# ESP.net
KiCad netlist of a schematic drawn in Altium Designer
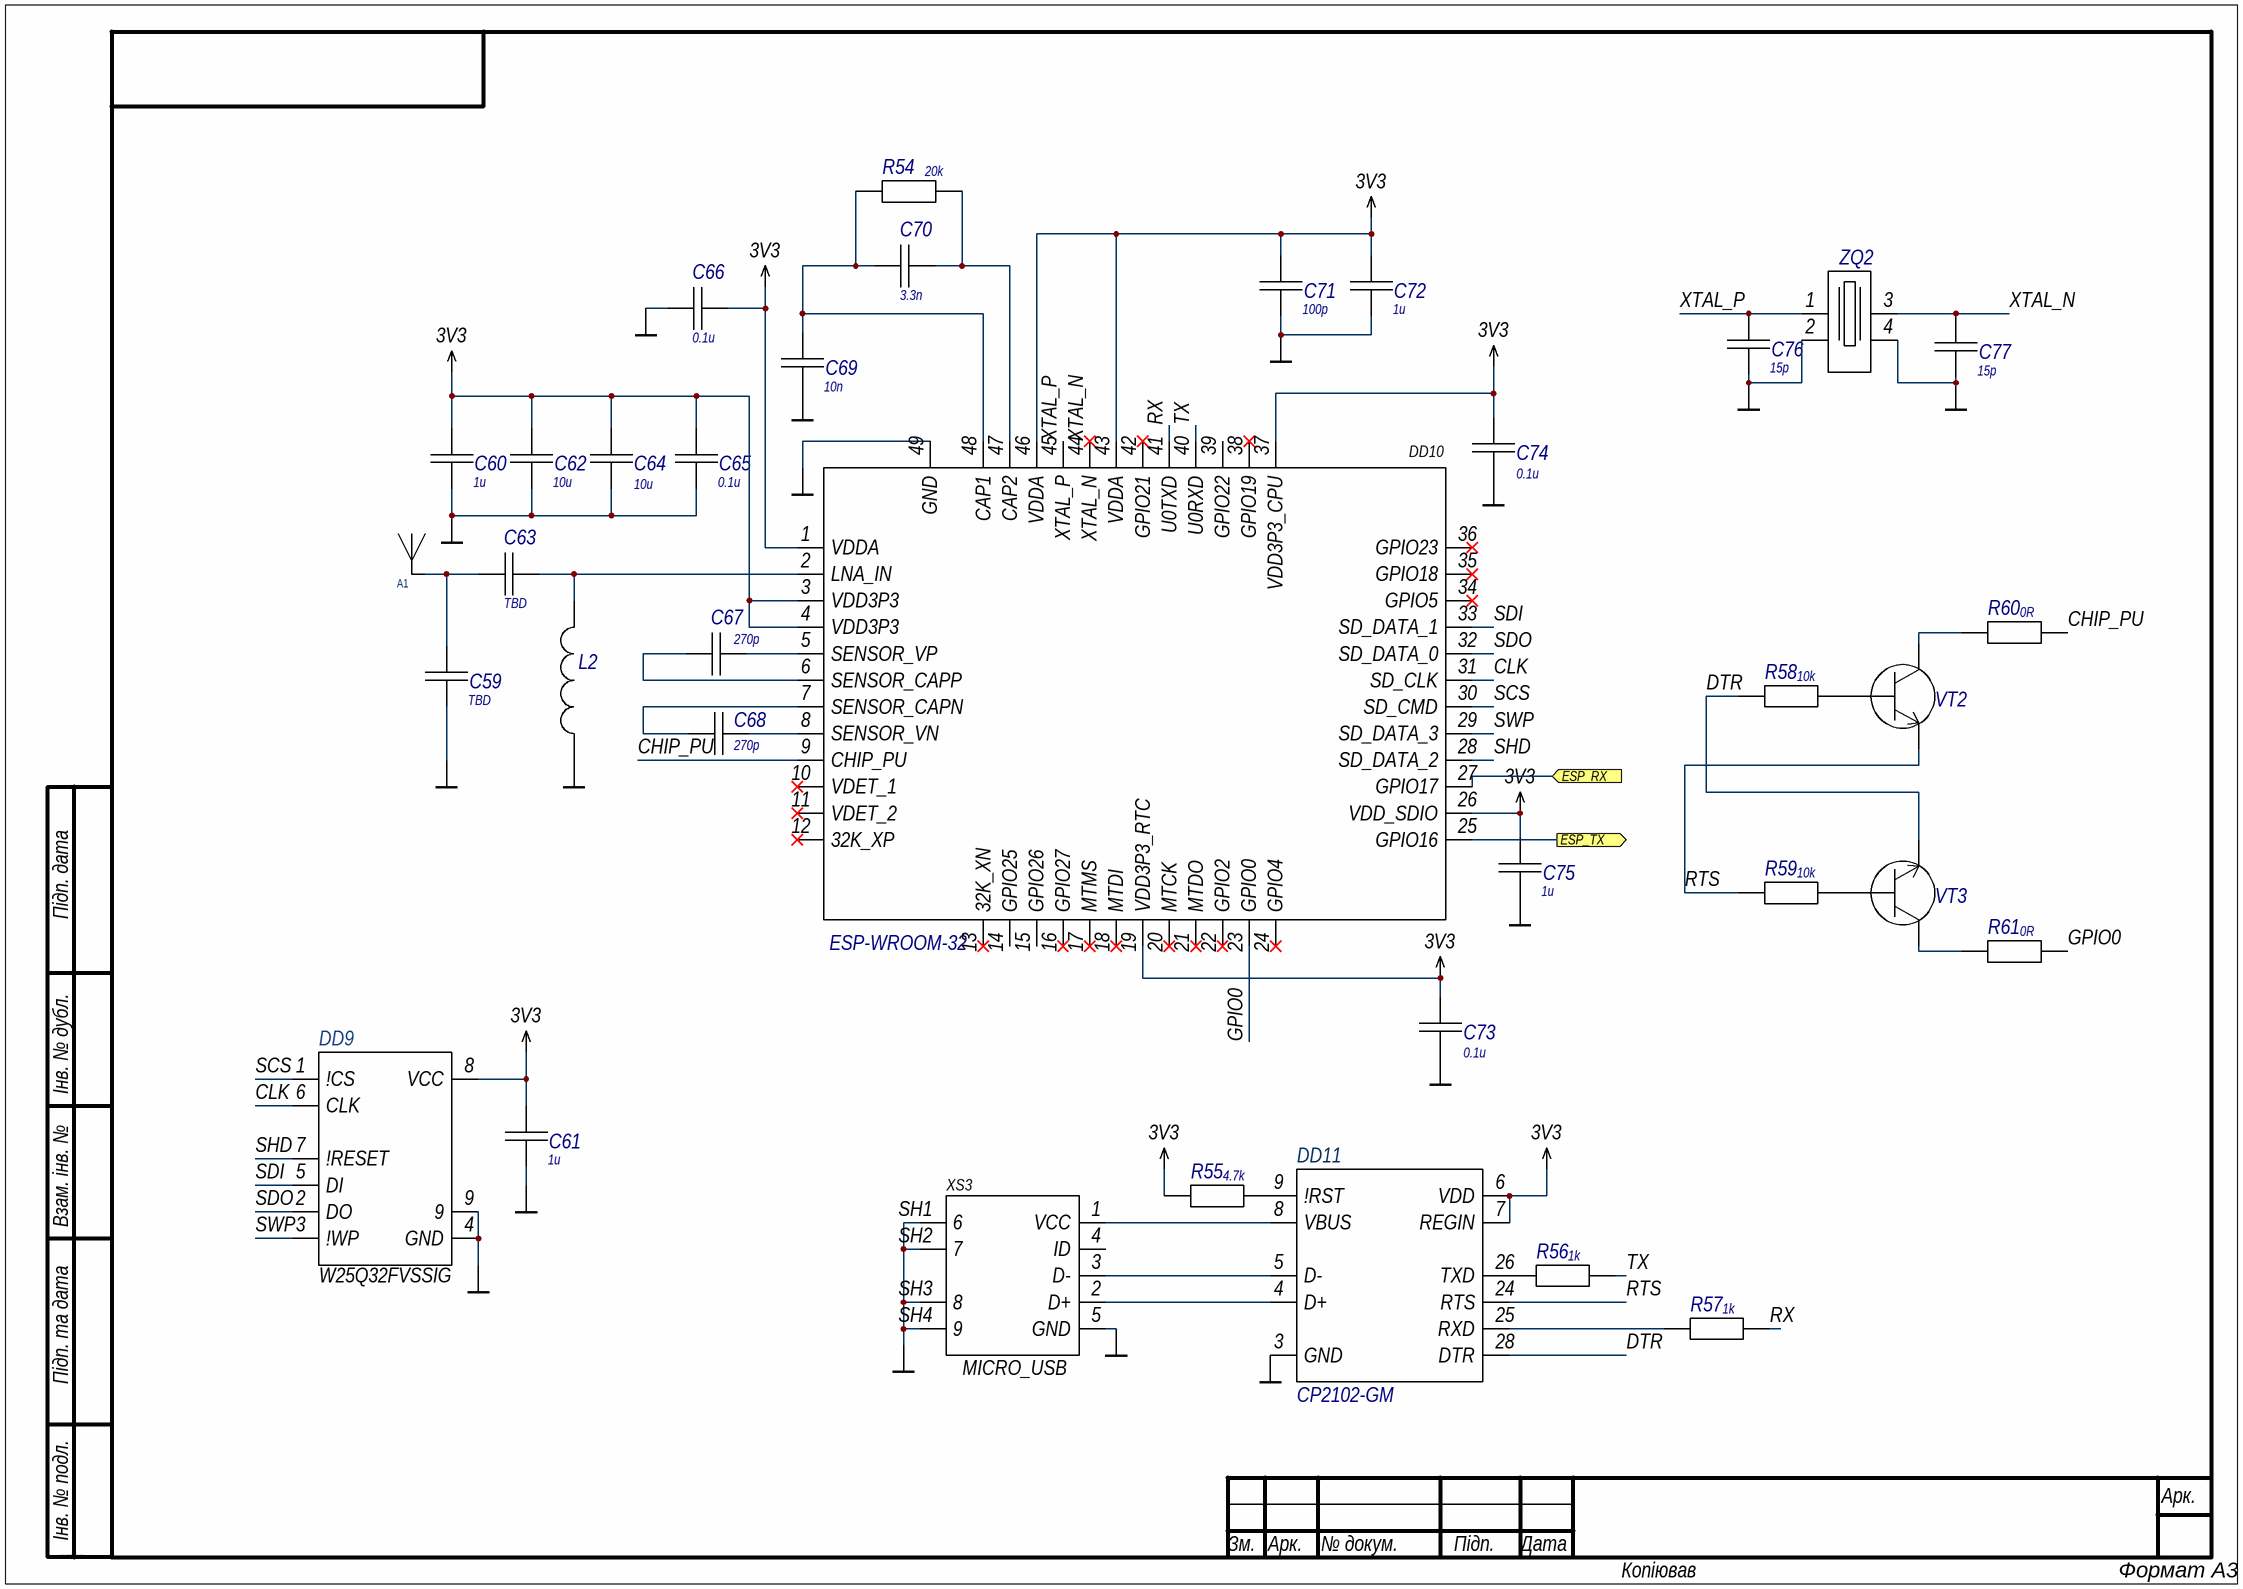
[diagram p0: ESP.SchDoc]

(export (version "E")
  (design (tool "Eeschema 10.0.6"))
  (components
    (comp (ref "A1")
      (value "Antenna-1-Pin")
      (description "SMA, Through-Hole")
      (libsource (lib "Schlib1") (part "Antenna-1-Pin"))
    )
    (comp (ref "C59")
      (value "TBD")
      (footprint "C_0603")
      (fields
        (field (name "VOLTAGE") "50 В")
        (field (name "TOLERANCE") "10%")
        (field (name "MANUFACTURER") "TDK Corporation")
      )
      (libsource (lib "Schlib1") (part "C_0603"))
    )
    (comp (ref "C60")
      (value "1u")
      (footprint "C_0603")
      (fields
        (field (name "VOLTAGE") "50 В")
        (field (name "TOLERANCE") "10%")
        (field (name "MANUFACTURER") "TDK Corporation")
      )
      (libsource (lib "Schlib1") (part "C_0603"))
    )
    (comp (ref "C61")
      (value "1u")
      (footprint "C_0603")
      (fields
        (field (name "VOLTAGE") "50 В")
        (field (name "TOLERANCE") "10%")
        (field (name "MANUFACTURER") "TDK Corporation")
      )
      (libsource (lib "Schlib1") (part "C_0603"))
    )
    (comp (ref "C62")
      (value "10u")
      (footprint "C_0603")
      (fields
        (field (name "VOLTAGE") "50 В")
        (field (name "TOLERANCE") "10%")
        (field (name "MANUFACTURER") "TDK Corporation")
      )
      (libsource (lib "Schlib1") (part "C_0603"))
    )
    (comp (ref "C63")
      (value "TBD")
      (footprint "C_0603")
      (fields
        (field (name "VOLTAGE") "50 В")
        (field (name "TOLERANCE") "10%")
        (field (name "MANUFACTURER") "TDK Corporation")
      )
      (libsource (lib "Schlib1") (part "C_0603"))
    )
    (comp (ref "C64")
      (value "10u")
      (footprint "C_0603")
      (fields
        (field (name "VOLTAGE") "50 В")
        (field (name "TOLERANCE") "10%")
        (field (name "MANUFACTURER") "TDK Corporation")
      )
      (libsource (lib "Schlib1") (part "C_0603"))
    )
    (comp (ref "C65")
      (value "0.1u")
      (footprint "C_0603")
      (fields
        (field (name "VOLTAGE") "50 В")
        (field (name "TOLERANCE") "10%")
        (field (name "MANUFACTURER") "TDK Corporation")
      )
      (libsource (lib "Schlib1") (part "C_0603"))
    )
    (comp (ref "C66")
      (value "0.1u")
      (footprint "C_0603")
      (fields
        (field (name "VOLTAGE") "50 В")
        (field (name "TOLERANCE") "10%")
        (field (name "MANUFACTURER") "TDK Corporation")
      )
      (libsource (lib "Schlib1") (part "C_0603"))
    )
    (comp (ref "C67")
      (value "270p")
      (footprint "C_0603")
      (fields
        (field (name "VOLTAGE") "50 В")
        (field (name "TOLERANCE") "10%")
        (field (name "MANUFACTURER") "TDK Corporation")
      )
      (libsource (lib "Schlib1") (part "C_0603"))
    )
    (comp (ref "C68")
      (value "270p")
      (footprint "C_0603")
      (fields
        (field (name "VOLTAGE") "50 В")
        (field (name "TOLERANCE") "10%")
        (field (name "MANUFACTURER") "TDK Corporation")
      )
      (libsource (lib "Schlib1") (part "C_0603"))
    )
    (comp (ref "C69")
      (value "10n")
      (footprint "C_0603")
      (fields
        (field (name "VOLTAGE") "50 В")
        (field (name "TOLERANCE") "10%")
        (field (name "MANUFACTURER") "TDK Corporation")
      )
      (libsource (lib "Schlib1") (part "C_0603"))
    )
    (comp (ref "C70")
      (value "3.3n")
      (footprint "C_0603")
      (fields
        (field (name "VOLTAGE") "50 В")
        (field (name "TOLERANCE") "10%")
        (field (name "MANUFACTURER") "TDK Corporation")
      )
      (libsource (lib "Schlib1") (part "C_0603"))
    )
    (comp (ref "C71")
      (value "100p")
      (footprint "C_0603")
      (fields
        (field (name "VOLTAGE") "50 В")
        (field (name "TOLERANCE") "10%")
        (field (name "MANUFACTURER") "TDK Corporation")
      )
      (libsource (lib "Schlib1") (part "C_0603"))
    )
    (comp (ref "C72")
      (value "1u")
      (footprint "C_0603")
      (fields
        (field (name "VOLTAGE") "50 В")
        (field (name "TOLERANCE") "10%")
        (field (name "MANUFACTURER") "TDK Corporation")
      )
      (libsource (lib "Schlib1") (part "C_0603"))
    )
    (comp (ref "C73")
      (value "0.1u")
      (footprint "C_0603")
      (fields
        (field (name "VOLTAGE") "50 В")
        (field (name "TOLERANCE") "10%")
        (field (name "MANUFACTURER") "TDK Corporation")
      )
      (libsource (lib "Schlib1") (part "C_0603"))
    )
    (comp (ref "C74")
      (value "0.1u")
      (footprint "C_0603")
      (fields
        (field (name "VOLTAGE") "50 В")
        (field (name "TOLERANCE") "10%")
        (field (name "MANUFACTURER") "TDK Corporation")
      )
      (libsource (lib "Schlib1") (part "C_0603"))
    )
    (comp (ref "C75")
      (value "1u")
      (footprint "C_0603")
      (fields
        (field (name "VOLTAGE") "50 В")
        (field (name "TOLERANCE") "10%")
        (field (name "MANUFACTURER") "TDK Corporation")
      )
      (libsource (lib "Schlib1") (part "C_0603"))
    )
    (comp (ref "C76")
      (value "15p")
      (footprint "C_0603")
      (fields
        (field (name "VOLTAGE") "50 В")
        (field (name "TOLERANCE") "10%")
        (field (name "MANUFACTURER") "TDK Corporation")
      )
      (libsource (lib "Schlib1") (part "C_0603"))
    )
    (comp (ref "C77")
      (value "15p")
      (footprint "C_0603")
      (fields
        (field (name "VOLTAGE") "50 В")
        (field (name "TOLERANCE") "10%")
        (field (name "MANUFACTURER") "TDK Corporation")
      )
      (libsource (lib "Schlib1") (part "C_0603"))
    )
    (comp (ref "DD9")
      (value "W25Q32FVSSIG")
      (footprint "W25QxxxJVEIQ-127P800X80_MED")
      (description "FLASH - NOR Memory IC 256Mb SPI - Quad I/O, QPI 133 MHz 8-WSON")
      (fields (field (name "MANUFACTURER") "Winbond Electronics") (field (name "PART NUMBER") "W25Q32FVSSIG"))
      (libsource (lib "Schlib1") (part "W25Q256JVEI1"))
    )
    (comp (ref "DD10")
      (value "ESP-WROOM-32 Espressif Systems")
      (fields (field (name "NAME") "ESP-WROOM-32") (field (name "MANUFACTURER") "Espressif Systems"))
      (libsource (lib "Schlib1") (part "ESP32-DOWDQ6"))
    )
    (comp (ref "DD11")
      (value "CP2102-GM")
      (footprint "QFN-28_5x5mm")
      (description "USB 2.0 to UART, 28-QFN (5x5)")
      (fields (field (name "MANUFACTURER") "Silicon Labs") (field (name "PART NUMBER") "CP2102-GM"))
      (libsource (lib "Schlib1") (part "CP2102-GM"))
    )
    (comp (ref "L2")
      (value "FCM 1608KF-601T03")
      (footprint "FB0603")
      (fields (field (name "MANUFACTURER") "TAI-TECH Advanced Electronics Co., Ltd."))
      (libsource (lib "Schlib1") (part "induction"))
    )
    (comp (ref "R54")
      (value "20k")
      (footprint "R0_0603")
      (fields
        (field (name "POWER") "0 В")
        (field (name "TOLERANCE") "1%")
        (field (name "MANUFACTURER") "Keystone Electronics")
      )
      (libsource (lib "Schlib1") (part "R_0603"))
    )
    (comp (ref "R55")
      (value "4.7k")
      (footprint "R0_0603")
      (fields
        (field (name "POWER") "0 В")
        (field (name "TOLERANCE") "1%")
        (field (name "MANUFACTURER") "Keystone Electronics")
      )
      (libsource (lib "Schlib1") (part "R_0603"))
    )
    (comp (ref "R56")
      (value "1k")
      (footprint "R0_0603")
      (fields
        (field (name "POWER") "0 В")
        (field (name "TOLERANCE") "1%")
        (field (name "MANUFACTURER") "Keystone Electronics")
      )
      (libsource (lib "Schlib1") (part "R_0603"))
    )
    (comp (ref "R57")
      (value "1k")
      (footprint "R0_0603")
      (fields
        (field (name "POWER") "0 В")
        (field (name "TOLERANCE") "1%")
        (field (name "MANUFACTURER") "Keystone Electronics")
      )
      (libsource (lib "Schlib1") (part "R_0603"))
    )
    (comp (ref "R58")
      (value "10k")
      (footprint "R0_0603")
      (fields
        (field (name "POWER") "0 В")
        (field (name "TOLERANCE") "1%")
        (field (name "MANUFACTURER") "Keystone Electronics")
      )
      (libsource (lib "Schlib1") (part "R_0603"))
    )
    (comp (ref "R59")
      (value "10k")
      (footprint "R0_0603")
      (fields
        (field (name "POWER") "0 В")
        (field (name "TOLERANCE") "1%")
        (field (name "MANUFACTURER") "Keystone Electronics")
      )
      (libsource (lib "Schlib1") (part "R_0603"))
    )
    (comp (ref "R60")
      (value "0R")
      (footprint "R0_0603")
      (fields
        (field (name "POWER") "0 В")
        (field (name "TOLERANCE") "1%")
        (field (name "MANUFACTURER") "Keystone Electronics")
      )
      (libsource (lib "Schlib1") (part "R_0603"))
    )
    (comp (ref "R61")
      (value "0R")
      (footprint "R0_0603")
      (fields
        (field (name "POWER") "0 В")
        (field (name "TOLERANCE") "1%")
        (field (name "MANUFACTURER") "Keystone Electronics")
      )
      (libsource (lib "Schlib1") (part "R_0603"))
    )
    (comp (ref "VT2")
      (value "MMBTA06LT1G")
      (footprint "SOT-23")
      (fields (field (name "MANUFACTURER") "onsemi"))
      (libsource (lib "Schlib1") (part "NPN"))
    )
    (comp (ref "VT3")
      (value "MMBTA06LT1G")
      (footprint "SOT-23")
      (fields (field (name "MANUFACTURER") "onsemi"))
      (libsource (lib "Schlib1") (part "NPN"))
    )
    (comp (ref "XS3")
      (value "MICRO_USB")
      (footprint "MICRO_USB")
      (fields (field (name "MANUFACTURER") "Amphenol ICC (FCI)"))
      (libsource (lib "Schlib1") (part "MICRO_USB"))
    )
    (comp (ref "ZQ2")
      (value "ABS25-32.768KHZ-6-T")
      (footprint "O2_768KHZ")
      (description "40MHz")
      (fields (field (name "MANUFACTURER") "Abracon LLC"))
      (libsource (lib "Schlib1") (part "CRYSTAL"))
    )
  )
  (nets
    (net (code "1") (name "/CHIP_PU") (class "Default")
      (node (ref "DD10") (pin "9") (pinfunction "CHIP_PU_9") (pintype "passive"))
      (node (ref "R60") (pin "2") (pinfunction "2_2") (pintype "passive"))
    )
    (net (code "2") (name "/CLK") (class "Default")
      (node (ref "DD10") (pin "31") (pinfunction "SD_CLK_31") (pintype "passive"))
      (node (ref "DD9") (pin "6") (pinfunction "CLK_6") (pintype "passive"))
    )
    (net (code "3") (name "/DTR") (class "Default")
      (node (ref "DD11") (pin "28") (pinfunction "DTR_28") (pintype "passive"))
      (node (ref "R58") (pin "1") (pinfunction "1_1") (pintype "passive"))
      (node (ref "VT3") (pin "2") (pinfunction "2_2") (pintype "passive"))
    )
    (net (code "4") (name "/ESP_RX") (class "Default")
      (node (ref "DD10") (pin "27") (pinfunction "GPIO17_27") (pintype "passive"))
    )
    (net (code "5") (name "/ESP_TX") (class "Default")
      (node (ref "DD10") (pin "25") (pinfunction "GPIO16_25") (pintype "passive"))
    )
    (net (code "6") (name "/GPIO0") (class "Default")
      (node (ref "DD10") (pin "23") (pinfunction "GPIO0_23") (pintype "passive"))
      (node (ref "R61") (pin "2") (pinfunction "2_2") (pintype "passive"))
    )
    (net (code "7") (name "/RTS") (class "Default")
      (node (ref "DD11") (pin "24") (pinfunction "RTS_24") (pintype "passive"))
      (node (ref "R59") (pin "1") (pinfunction "1_1") (pintype "passive"))
      (node (ref "VT2") (pin "2") (pinfunction "2_2") (pintype "passive"))
    )
    (net (code "8") (name "/RX") (class "Default")
      (node (ref "DD10") (pin "41") (pinfunction "U0TXD_41") (pintype "passive"))
      (node (ref "R57") (pin "2") (pinfunction "2_2") (pintype "passive"))
    )
    (net (code "9") (name "/SCS") (class "Default")
      (node (ref "DD10") (pin "30") (pinfunction "SD_CMD_30") (pintype "passive"))
      (node (ref "DD9") (pin "1") (pinfunction "!CS_1") (pintype "passive"))
    )
    (net (code "10") (name "/SDI") (class "Default")
      (node (ref "DD10") (pin "33") (pinfunction "SD_DATA_1_33") (pintype "passive"))
      (node (ref "DD9") (pin "5") (pinfunction "DI_5") (pintype "passive"))
    )
    (net (code "11") (name "/SDO") (class "Default")
      (node (ref "DD10") (pin "32") (pinfunction "SD_DATA_0_32") (pintype "passive"))
      (node (ref "DD9") (pin "2") (pinfunction "DO_2") (pintype "passive"))
    )
    (net (code "12") (name "/SHD") (class "Default")
      (node (ref "DD10") (pin "28") (pinfunction "SD_DATA_2_28") (pintype "passive"))
      (node (ref "DD9") (pin "7") (pinfunction "!RESET_7") (pintype "passive"))
    )
    (net (code "13") (name "/SWP") (class "Default")
      (node (ref "DD10") (pin "29") (pinfunction "SD_DATA_3_29") (pintype "passive"))
      (node (ref "DD9") (pin "3") (pinfunction "!WP_3") (pintype "passive"))
    )
    (net (code "14") (name "/TX") (class "Default")
      (node (ref "DD10") (pin "40") (pinfunction "U0RXD_40") (pintype "passive"))
      (node (ref "R56") (pin "2") (pinfunction "2_2") (pintype "passive"))
    )
    (net (code "15") (name "/XTAL_N") (class "Default")
      (node (ref "C77") (pin "2") (pinfunction "2_2") (pintype "passive"))
      (node (ref "DD10") (pin "44") (pinfunction "XTAL_N_44") (pintype "passive"))
      (node (ref "ZQ2") (pin "3") (pinfunction "3_3") (pintype "passive"))
    )
    (net (code "16") (name "/XTAL_P") (class "Default")
      (node (ref "C76") (pin "2") (pinfunction "2_2") (pintype "passive"))
      (node (ref "DD10") (pin "45") (pinfunction "XTAL_P_45") (pintype "passive"))
      (node (ref "ZQ2") (pin "1") (pinfunction "1_1") (pintype "passive"))
    )
    (net (code "17") (name "3V3") (class "Default")
      (node (ref "C60") (pin "2") (pinfunction "2_2") (pintype "passive"))
      (node (ref "C61") (pin "2") (pinfunction "2_2") (pintype "passive"))
      (node (ref "C62") (pin "2") (pinfunction "2_2") (pintype "passive"))
      (node (ref "C64") (pin "1") (pinfunction "1_1") (pintype "passive"))
      (node (ref "C65") (pin "2") (pinfunction "2_2") (pintype "passive"))
      (node (ref "C66") (pin "1") (pinfunction "1_1") (pintype "passive"))
      (node (ref "C71") (pin "2") (pinfunction "2_2") (pintype "passive"))
      (node (ref "C72") (pin "2") (pinfunction "2_2") (pintype "passive"))
      (node (ref "C73") (pin "1") (pinfunction "1_1") (pintype "passive"))
      (node (ref "C74") (pin "1") (pinfunction "1_1") (pintype "passive"))
      (node (ref "C75") (pin "2") (pinfunction "2_2") (pintype "passive"))
      (node (ref "DD10") (pin "1") (pinfunction "VDDA_1") (pintype "passive"))
      (node (ref "DD10") (pin "19") (pinfunction "VDD3P3_RTC_19") (pintype "passive"))
      (node (ref "DD10") (pin "26") (pinfunction "VDD_SDIO_26") (pintype "passive"))
      (node (ref "DD10") (pin "3") (pinfunction "VDD3P3_3") (pintype "passive"))
      (node (ref "DD10") (pin "37") (pinfunction "VDD3P3_CPU_37") (pintype "passive"))
      (node (ref "DD10") (pin "4") (pinfunction "VDD3P3_4") (pintype "passive"))
      (node (ref "DD10") (pin "43") (pinfunction "VDDA_43") (pintype "passive"))
      (node (ref "DD10") (pin "46") (pinfunction "VDDA_46") (pintype "passive"))
      (node (ref "DD11") (pin "6") (pinfunction "VDD_6") (pintype "passive"))
      (node (ref "DD11") (pin "7") (pinfunction "REGIN_7") (pintype "passive"))
      (node (ref "DD9") (pin "8") (pinfunction "VCC_8") (pintype "passive"))
      (node (ref "R55") (pin "1") (pinfunction "1_1") (pintype "passive"))
    )
    (net (code "18") (name "GND") (class "Default")
      (node (ref "C59") (pin "1") (pinfunction "1_1") (pintype "passive"))
      (node (ref "C60") (pin "1") (pinfunction "1_1") (pintype "passive"))
      (node (ref "C61") (pin "1") (pinfunction "1_1") (pintype "passive"))
      (node (ref "C62") (pin "1") (pinfunction "1_1") (pintype "passive"))
      (node (ref "C64") (pin "2") (pinfunction "2_2") (pintype "passive"))
      (node (ref "C65") (pin "1") (pinfunction "1_1") (pintype "passive"))
      (node (ref "C66") (pin "2") (pinfunction "2_2") (pintype "passive"))
      (node (ref "C69") (pin "1") (pinfunction "1_1") (pintype "passive"))
      (node (ref "C71") (pin "1") (pinfunction "1_1") (pintype "passive"))
      (node (ref "C72") (pin "1") (pinfunction "1_1") (pintype "passive"))
      (node (ref "C73") (pin "2") (pinfunction "2_2") (pintype "passive"))
      (node (ref "C74") (pin "2") (pinfunction "2_2") (pintype "passive"))
      (node (ref "C75") (pin "1") (pinfunction "1_1") (pintype "passive"))
      (node (ref "C76") (pin "1") (pinfunction "1_1") (pintype "passive"))
      (node (ref "C77") (pin "1") (pinfunction "1_1") (pintype "passive"))
      (node (ref "DD10") (pin "49") (pinfunction "GND_49") (pintype "passive"))
      (node (ref "DD11") (pin "3") (pinfunction "GND_3") (pintype "passive"))
      (node (ref "DD9") (pin "4") (pinfunction "GND_4") (pintype "passive"))
      (node (ref "DD9") (pin "9") (pinfunction "9_9") (pintype "passive"))
      (node (ref "L2") (pin "1") (pinfunction "1_1") (pintype "passive"))
      (node (ref "XS3") (pin "5") (pinfunction "GND_5") (pintype "passive"))
      (node (ref "XS3") (pin "SH1") (pinfunction "6_SH1") (pintype "passive"))
      (node (ref "XS3") (pin "SH2") (pinfunction "7_SH2") (pintype "passive"))
      (node (ref "XS3") (pin "SH3") (pinfunction "8_SH3") (pintype "passive"))
      (node (ref "XS3") (pin "SH4") (pinfunction "9_SH4") (pintype "passive"))
      (node (ref "ZQ2") (pin "2") (pinfunction "2_2") (pintype "passive"))
      (node (ref "ZQ2") (pin "4") (pinfunction "4_4") (pintype "passive"))
    )
    (net (code "19") (name "Net-(A1-Pad1)") (class "Default")
      (node (ref "A1") (pin "1") (pintype "passive"))
      (node (ref "C59") (pin "2") (pinfunction "2_2") (pintype "passive"))
      (node (ref "C63") (pin "2") (pinfunction "2_2") (pintype "passive"))
    )
    (net (code "20") (name "Net-(DD10-CAP1)") (class "Default")
      (node (ref "C69") (pin "2") (pinfunction "2_2") (pintype "passive"))
      (node (ref "C70") (pin "2") (pinfunction "2_2") (pintype "passive"))
      (node (ref "DD10") (pin "48") (pinfunction "CAP1_48") (pintype "passive"))
      (node (ref "R54") (pin "1") (pinfunction "1_1") (pintype "passive"))
    )
    (net (code "21") (name "Net-(DD10-CAP2)") (class "Default")
      (node (ref "C70") (pin "1") (pinfunction "1_1") (pintype "passive"))
      (node (ref "DD10") (pin "47") (pinfunction "CAP2_47") (pintype "passive"))
      (node (ref "R54") (pin "2") (pinfunction "2_2") (pintype "passive"))
    )
    (net (code "22") (name "Net-(DD10-LNA_IN)") (class "Default")
      (node (ref "C63") (pin "1") (pinfunction "1_1") (pintype "passive"))
      (node (ref "DD10") (pin "2") (pinfunction "LNA_IN_2") (pintype "passive"))
      (node (ref "L2") (pin "2") (pinfunction "2_2") (pintype "passive"))
    )
    (net (code "23") (name "Net-(DD10-SENSOR_CAPN)") (class "Default")
      (node (ref "C68") (pin "2") (pinfunction "2_2") (pintype "passive"))
      (node (ref "DD10") (pin "7") (pinfunction "SENSOR_CAPN_7") (pintype "passive"))
    )
    (net (code "24") (name "Net-(DD10-SENSOR_CAPP)") (class "Default")
      (node (ref "C67") (pin "2") (pinfunction "2_2") (pintype "passive"))
      (node (ref "DD10") (pin "6") (pinfunction "SENSOR_CAPP_6") (pintype "passive"))
    )
    (net (code "25") (name "Net-(DD10-SENSOR_VN)") (class "Default")
      (node (ref "C68") (pin "1") (pinfunction "1_1") (pintype "passive"))
      (node (ref "DD10") (pin "8") (pinfunction "SENSOR_VN_8") (pintype "passive"))
    )
    (net (code "26") (name "Net-(DD10-SENSOR_VP)") (class "Default")
      (node (ref "C67") (pin "1") (pinfunction "1_1") (pintype "passive"))
      (node (ref "DD10") (pin "5") (pinfunction "SENSOR_VP_5") (pintype "passive"))
    )
    (net (code "27") (name "Net-(DD11-!RST)") (class "Default")
      (node (ref "DD11") (pin "9") (pinfunction "!RST_9") (pintype "passive"))
      (node (ref "R55") (pin "2") (pinfunction "2_2") (pintype "passive"))
    )
    (net (code "28") (name "Net-(DD11-D+)") (class "Default")
      (node (ref "DD11") (pin "4") (pinfunction "D+_4") (pintype "passive"))
      (node (ref "XS3") (pin "2") (pinfunction "D+_2") (pintype "passive"))
    )
    (net (code "29") (name "Net-(DD11-D-)") (class "Default")
      (node (ref "DD11") (pin "5") (pinfunction "D-_5") (pintype "passive"))
      (node (ref "XS3") (pin "3") (pinfunction "D-_3") (pintype "passive"))
    )
    (net (code "30") (name "Net-(DD11-RXD)") (class "Default")
      (node (ref "DD11") (pin "25") (pinfunction "RXD_25") (pintype "passive"))
      (node (ref "R57") (pin "1") (pinfunction "1_1") (pintype "passive"))
    )
    (net (code "31") (name "Net-(DD11-TXD)") (class "Default")
      (node (ref "DD11") (pin "26") (pinfunction "TXD_26") (pintype "passive"))
      (node (ref "R56") (pin "1") (pinfunction "1_1") (pintype "passive"))
    )
    (net (code "32") (name "Net-(DD11-VBUS)") (class "Default")
      (node (ref "DD11") (pin "8") (pinfunction "VBUS_8") (pintype "passive"))
      (node (ref "XS3") (pin "1") (pinfunction "VCC_1") (pintype "passive"))
    )
    (net (code "33") (name "Net-(R58-Pad2)") (class "Default")
      (node (ref "R58") (pin "2") (pinfunction "2_2") (pintype "passive"))
      (node (ref "VT2") (pin "3") (pinfunction "3_3") (pintype "passive"))
    )
    (net (code "34") (name "Net-(R59-Pad2)") (class "Default")
      (node (ref "R59") (pin "2") (pinfunction "2_2") (pintype "passive"))
      (node (ref "VT3") (pin "3") (pinfunction "3_3") (pintype "passive"))
    )
    (net (code "35") (name "Net-(R60-Pad1)") (class "Default")
      (node (ref "R60") (pin "1") (pinfunction "1_1") (pintype "passive"))
      (node (ref "VT2") (pin "1") (pinfunction "1_1") (pintype "passive"))
    )
    (net (code "36") (name "Net-(R61-Pad1)") (class "Default")
      (node (ref "R61") (pin "1") (pinfunction "1_1") (pintype "passive"))
      (node (ref "VT3") (pin "1") (pinfunction "1_1") (pintype "passive"))
    )
    (net (code "37") (name "unconnected-(DD10-32K_XN-Pad13)") (class "Default")
      (node (ref "DD10") (pin "13") (pinfunction "32K_XN_13") (pintype "passive+no_connect"))
    )
    (net (code "38") (name "unconnected-(DD10-32K_XP-Pad12)") (class "Default")
      (node (ref "DD10") (pin "12") (pinfunction "32K_XP_12") (pintype "passive+no_connect"))
    )
    (net (code "39") (name "unconnected-(DD10-GPIO2-Pad22)") (class "Default")
      (node (ref "DD10") (pin "22") (pinfunction "GPIO2_22") (pintype "passive+no_connect"))
    )
    (net (code "40") (name "unconnected-(DD10-GPIO4-Pad24)") (class "Default")
      (node (ref "DD10") (pin "24") (pinfunction "GPIO4_24") (pintype "passive+no_connect"))
    )
    (net (code "41") (name "unconnected-(DD10-GPIO5-Pad34)") (class "Default")
      (node (ref "DD10") (pin "34") (pinfunction "GPIO5_34") (pintype "passive+no_connect"))
    )
    (net (code "42") (name "unconnected-(DD10-GPIO18-Pad35)") (class "Default")
      (node (ref "DD10") (pin "35") (pinfunction "GPIO18_35") (pintype "passive+no_connect"))
    )
    (net (code "43") (name "unconnected-(DD10-GPIO19-Pad38)") (class "Default")
      (node (ref "DD10") (pin "38") (pinfunction "GPIO19_38") (pintype "passive+no_connect"))
    )
    (net (code "44") (name "unconnected-(DD10-GPIO21-Pad42)") (class "Default")
      (node (ref "DD10") (pin "42") (pinfunction "GPIO21_42") (pintype "passive+no_connect"))
    )
    (net (code "45") (name "unconnected-(DD10-GPIO22-Pad39)") (class "Default")
      (node (ref "DD10") (pin "39") (pinfunction "GPIO22_39") (pintype "passive"))
    )
    (net (code "46") (name "unconnected-(DD10-GPIO23-Pad36)") (class "Default")
      (node (ref "DD10") (pin "36") (pinfunction "GPIO23_36") (pintype "passive+no_connect"))
    )
    (net (code "47") (name "unconnected-(DD10-GPIO25-Pad14)") (class "Default")
      (node (ref "DD10") (pin "14") (pinfunction "GPIO25_14") (pintype "passive"))
    )
    (net (code "48") (name "unconnected-(DD10-GPIO26-Pad15)") (class "Default")
      (node (ref "DD10") (pin "15") (pinfunction "GPIO26_15") (pintype "passive"))
    )
    (net (code "49") (name "unconnected-(DD10-GPIO27-Pad16)") (class "Default")
      (node (ref "DD10") (pin "16") (pinfunction "GPIO27_16") (pintype "passive+no_connect"))
    )
    (net (code "50") (name "unconnected-(DD10-MTCK-Pad20)") (class "Default")
      (node (ref "DD10") (pin "20") (pinfunction "MTCK_20") (pintype "passive+no_connect"))
    )
    (net (code "51") (name "unconnected-(DD10-MTDI-Pad18)") (class "Default")
      (node (ref "DD10") (pin "18") (pinfunction "MTDI_18") (pintype "passive+no_connect"))
    )
    (net (code "52") (name "unconnected-(DD10-MTDO-Pad21)") (class "Default")
      (node (ref "DD10") (pin "21") (pinfunction "MTDO_21") (pintype "passive+no_connect"))
    )
    (net (code "53") (name "unconnected-(DD10-MTMS-Pad17)") (class "Default")
      (node (ref "DD10") (pin "17") (pinfunction "MTMS_17") (pintype "passive+no_connect"))
    )
    (net (code "54") (name "unconnected-(DD10-VDET_1-Pad10)") (class "Default")
      (node (ref "DD10") (pin "10") (pinfunction "VDET_1_10") (pintype "passive+no_connect"))
    )
    (net (code "55") (name "unconnected-(DD10-VDET_2-Pad11)") (class "Default")
      (node (ref "DD10") (pin "11") (pinfunction "VDET_2_11") (pintype "passive+no_connect"))
    )
    (net (code "56") (name "unconnected-(XS3-ID-Pad4)") (class "Default")
      (node (ref "XS3") (pin "4") (pinfunction "ID_4") (pintype "passive"))
    )
  )
)
